# MCU_ATMEGA328P.net
KiCad netlist of a schematic drawn in Altium Designer
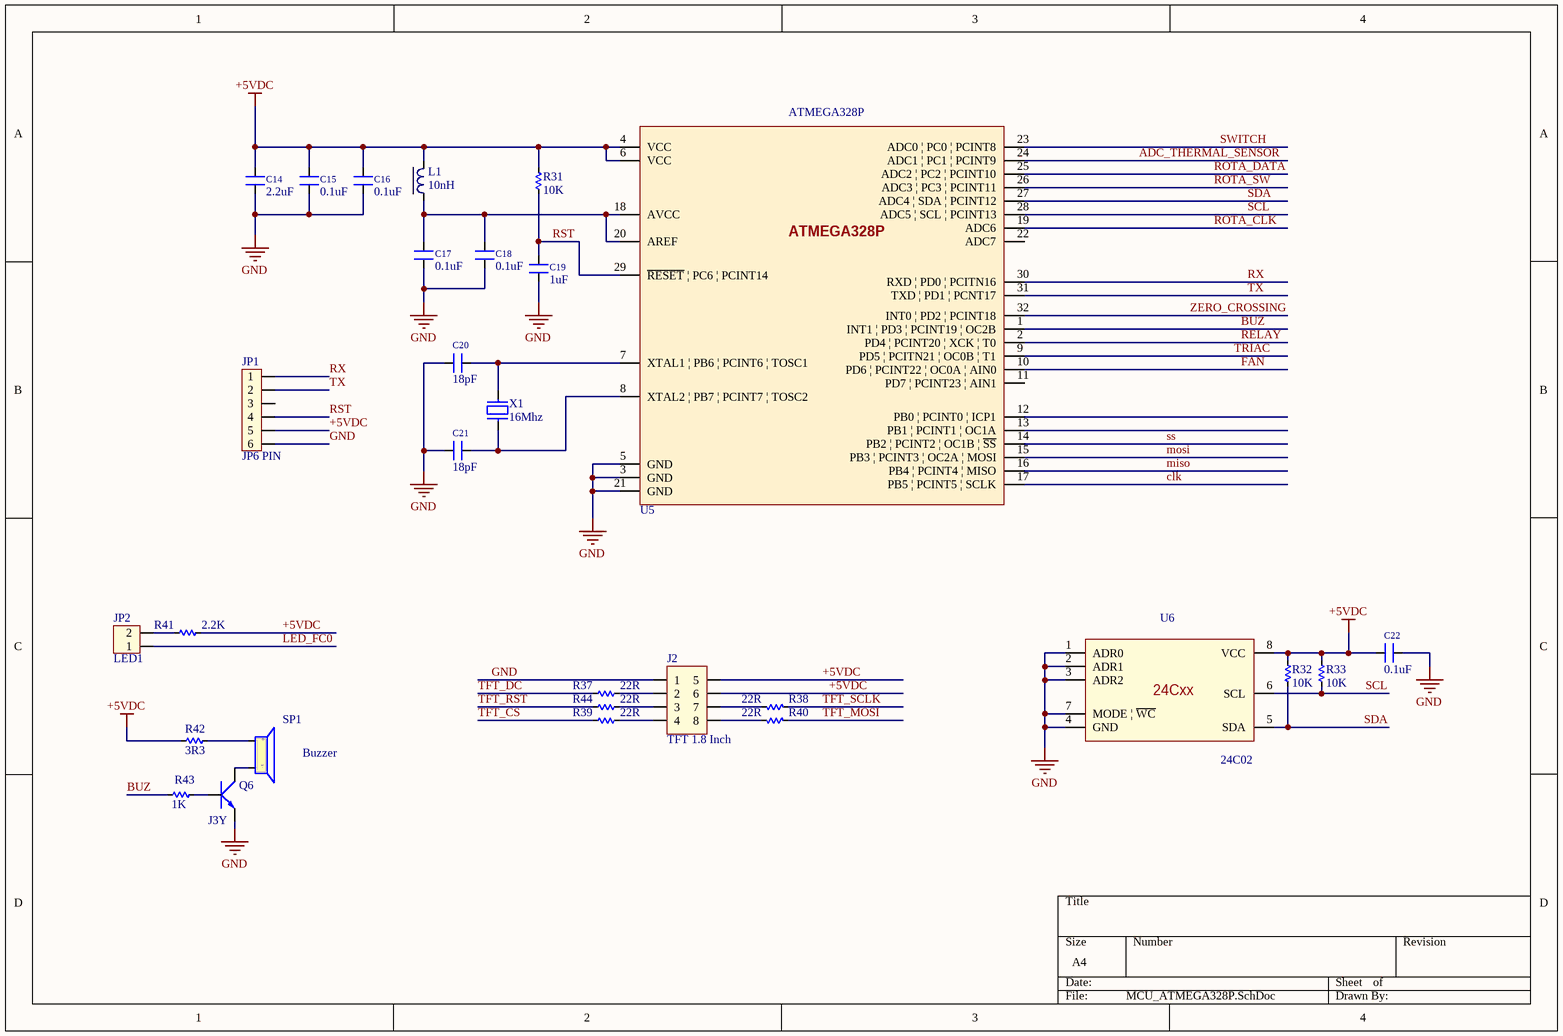
[diagram p0: MCU_ATMEGA328P.SchDoc]

(export (version "E")
  (design (tool "Eeschema 10.0.6"))
  (components
    (comp (ref "C14")
      (value "2.2uF")
      (footprint "CN-SMD-1206")
      (description "CAP SMD")
      (fields (field (name "DESIGNED BY") "VanDungEvn"))
      (libsource (lib "Sang_Library") (part "CAP SMD"))
    )
    (comp (ref "C15")
      (value "0.1uF")
      (footprint "CN-SMD-0805")
      (description "CAP SMD")
      (fields (field (name "DESIGNED BY") "VanDungEvn"))
      (libsource (lib "Sang_Library") (part "CAP SMD"))
    )
    (comp (ref "C16")
      (value "0.1uF")
      (footprint "CN-SMD-0805")
      (description "CAP SMD")
      (fields (field (name "DESIGNED BY") "VanDungEvn"))
      (libsource (lib "Sang_Library") (part "CAP SMD"))
    )
    (comp (ref "C17")
      (value "0.1uF")
      (footprint "CN-SMD-0805")
      (description "CAP SMD")
      (fields (field (name "DESIGNED BY") "VanDungEvn"))
      (libsource (lib "Sang_Library") (part "CAP SMD"))
    )
    (comp (ref "C18")
      (value "0.1uF")
      (footprint "CN-SMD-0805")
      (description "CAP SMD")
      (fields (field (name "DESIGNED BY") "VanDungEvn"))
      (libsource (lib "Sang_Library") (part "CAP SMD"))
    )
    (comp (ref "C19")
      (value "1uF")
      (footprint "CN-SMD-0805")
      (description "CAP SMD")
      (fields (field (name "DESIGNED BY") "VanDungEvn"))
      (libsource (lib "Sang_Library") (part "CAP SMD"))
    )
    (comp (ref "C20")
      (value "18pF")
      (footprint "CN-SMD-0805")
      (description "CAP SMD")
      (fields (field (name "DESIGNED BY") "VanDungEvn"))
      (libsource (lib "Sang_Library") (part "CAP SMD"))
    )
    (comp (ref "C21")
      (value "18pF")
      (footprint "CN-SMD-0805")
      (description "CAP SMD")
      (fields (field (name "DESIGNED BY") "VanDungEvn"))
      (libsource (lib "Sang_Library") (part "CAP SMD"))
    )
    (comp (ref "C22")
      (value "0.1uF")
      (footprint "CN-SMD-0805")
      (description "CAP SMD")
      (fields (field (name "DESIGNED BY") "VanDungEvn"))
      (libsource (lib "Sang_Library") (part "CAP SMD"))
    )
    (comp (ref "J2")
      (value "TFT 1.8 Inch")
      (footprint "JP4x2")
      (description "Connector 4x2")
      (libsource (lib "Sang_Library") (part "JP4x2"))
    )
    (comp (ref "JP1") (value "JP6 PIN") (footprint "JP6") (libsource (lib "Sang_Library") (part "JP6")))
    (comp (ref "JP2")
      (value "LED1")
      (footprint "CON2")
      (description "Connector 2")
      (libsource (lib "syhaunguyen") (part "Con2"))
    )
    (comp (ref "L1")
      (value "10nH")
      (footprint "IN-SMD-0805")
      (description "inductor-SMD")
      (libsource (lib "Sang_Library") (part "inductor-SMD"))
    )
    (comp (ref "Q6")
      (value "J3Y")
      (footprint "SOT23B")
      (description "NPN 600mW, ECB")
      (libsource (lib "Sang_Library") (part "2N222"))
    )
    (comp (ref "R31")
      (value "10K")
      (footprint "RES-SMD-0603")
      (description "Resistor")
      (fields
        (field (name "MANUFACTURER") "Generic Components")
        (field (name "PUBLISHER") "Altium Hobart Technology Centre")
      )
      (libsource (lib "Sang_Library") (part "Res-SMD"))
    )
    (comp (ref "R32")
      (value "10K")
      (footprint "RES-SMD-0603")
      (description "Resistor")
      (fields
        (field (name "MANUFACTURER") "Generic Components")
        (field (name "PUBLISHER") "Altium Hobart Technology Centre")
      )
      (libsource (lib "Sang_Library") (part "Res-SMD"))
    )
    (comp (ref "R33")
      (value "10K")
      (footprint "RES-SMD-0603")
      (description "Resistor")
      (fields
        (field (name "MANUFACTURER") "Generic Components")
        (field (name "PUBLISHER") "Altium Hobart Technology Centre")
      )
      (libsource (lib "Sang_Library") (part "Res-SMD"))
    )
    (comp (ref "R37")
      (value "22R")
      (footprint "RES-SMD-0603")
      (description "Resistor")
      (fields
        (field (name "MANUFACTURER") "Generic Components")
        (field (name "PUBLISHER") "Altium Hobart Technology Centre")
      )
      (libsource (lib "Sang_Library") (part "Res-SMD"))
    )
    (comp (ref "R38")
      (value "22R")
      (footprint "RES-SMD-0603")
      (description "Resistor")
      (fields
        (field (name "MANUFACTURER") "Generic Components")
        (field (name "PUBLISHER") "Altium Hobart Technology Centre")
      )
      (libsource (lib "Sang_Library") (part "Res-SMD"))
    )
    (comp (ref "R39")
      (value "22R")
      (footprint "RES-SMD-0603")
      (description "Resistor")
      (fields
        (field (name "MANUFACTURER") "Generic Components")
        (field (name "PUBLISHER") "Altium Hobart Technology Centre")
      )
      (libsource (lib "Sang_Library") (part "Res-SMD"))
    )
    (comp (ref "R40")
      (value "22R")
      (footprint "RES-SMD-0603")
      (description "Resistor")
      (fields
        (field (name "MANUFACTURER") "Generic Components")
        (field (name "PUBLISHER") "Altium Hobart Technology Centre")
      )
      (libsource (lib "Sang_Library") (part "Res-SMD"))
    )
    (comp (ref "R41")
      (value "2.2K")
      (footprint "RES-SMD-0603")
      (description "Resistor")
      (fields
        (field (name "MANUFACTURER") "Generic Components")
        (field (name "PUBLISHER") "Altium Hobart Technology Centre")
      )
      (libsource (lib "Sang_Library") (part "Res-SMD"))
    )
    (comp (ref "R42")
      (value "3R3")
      (footprint "RES-SMD-0805")
      (description "Resistor")
      (fields
        (field (name "MANUFACTURER") "Generic Components")
        (field (name "PUBLISHER") "Altium Hobart Technology Centre")
      )
      (libsource (lib "Sang_Library") (part "Res-SMD"))
    )
    (comp (ref "R43")
      (value "1K")
      (footprint "RES-SMD-0805")
      (description "Resistor")
      (fields
        (field (name "MANUFACTURER") "Generic Components")
        (field (name "PUBLISHER") "Altium Hobart Technology Centre")
      )
      (libsource (lib "Sang_Library") (part "Res-SMD"))
    )
    (comp (ref "R44")
      (value "22R")
      (footprint "RES-SMD-0603")
      (description "Resistor")
      (fields
        (field (name "MANUFACTURER") "Generic Components")
        (field (name "PUBLISHER") "Altium Hobart Technology Centre")
      )
      (libsource (lib "Sang_Library") (part "Res-SMD"))
    )
    (comp (ref "SP1") (value "Buzzer") (footprint "Buzzer") (libsource (lib "Huan") (part "Buzzer_5V")))
    (comp (ref "U5") (value "ATMEGA328P") (footprint "TQFP-32") (libsource (lib "Huan") (part "ATMEGA328p")))
    (comp (ref "U6")
      (value "24C02")
      (footprint "SOP-8")
      (description "SERIAL EEPROM")
      (libsource (lib "Huan") (part "24Cxx"))
    )
    (comp (ref "X1")
      (value "16Mhz")
      (footprint "XT-49S/DIP")
      (description "crystal")
      (libsource (lib "Sang_Library") (part "XTAL"))
    )
  )
  (nets
    (net (code "1") (name "+5VDC") (class "Default")
      (node (ref "C14") (pin "2") (pinfunction "2_2") (pintype "passive"))
      (node (ref "C15") (pin "2") (pinfunction "2_2") (pintype "passive"))
      (node (ref "C16") (pin "2") (pinfunction "2_2") (pintype "passive"))
      (node (ref "C22") (pin "2") (pinfunction "2_2") (pintype "passive"))
      (node (ref "J2") (pin "5") (pinfunction "5_5") (pintype "passive"))
      (node (ref "J2") (pin "6") (pinfunction "6_6") (pintype "passive"))
      (node (ref "JP1") (pin "5") (pinfunction "5_5") (pintype "passive"))
      (node (ref "L1") (pin "2") (pinfunction "2_2") (pintype "passive"))
      (node (ref "R31") (pin "1") (pinfunction "1_1") (pintype "passive"))
      (node (ref "R32") (pin "1") (pinfunction "1_1") (pintype "passive"))
      (node (ref "R33") (pin "1") (pinfunction "1_1") (pintype "passive"))
      (node (ref "R41") (pin "2") (pinfunction "2_2") (pintype "passive"))
      (node (ref "R42") (pin "1") (pinfunction "1_1") (pintype "passive"))
      (node (ref "U5") (pin "4") (pinfunction "VCC_4") (pintype "passive"))
      (node (ref "U5") (pin "6") (pinfunction "VCC_6") (pintype "passive"))
      (node (ref "U6") (pin "8") (pinfunction "VCC_8") (pintype "passive"))
    )
    (net (code "3") (name "/ADC_THERMAL_SENSOR") (class "Default")
      (node (ref "U5") (pin "24") (pinfunction "ADC1_¦_PC1_¦_PCINT9_24") (pintype "passive"))
    )
    (net (code "4") (name "/BUZ") (class "Default")
      (node (ref "R43") (pin "2") (pinfunction "2_2") (pintype "passive"))
      (node (ref "U5") (pin "1") (pinfunction "INT1_¦_PD3_¦_PCINT19_¦_OC2B_1") (pintype "power_in"))
    )
    (net (code "5") (name "/FAN") (class "Default")
      (node (ref "U5") (pin "10") (pinfunction "PD6_¦_PCINT22_¦_OC0A_¦_AIN0_10") (pintype "power_in"))
    )
    (net (code "6") (name "/LED_FC0") (class "Default")
      (node (ref "JP2") (pin "1") (pinfunction "1_1") (pintype "passive"))
    )
    (net (code "7") (name "/RELAY") (class "Default")
      (node (ref "U5") (pin "2") (pinfunction "PD4_¦_PCINT20_¦_XCK_¦_T0_2") (pintype "passive"))
    )
    (net (code "8") (name "/ROTA_CLK") (class "Default")
      (node (ref "U5") (pin "19") (pinfunction "ADC6_19") (pintype "passive"))
    )
    (net (code "9") (name "/ROTA_DATA") (class "Default")
      (node (ref "U5") (pin "25") (pinfunction "ADC2_¦_PC2_¦_PCINT10_25") (pintype "passive"))
    )
    (net (code "10") (name "/ROTA_SW") (class "Default")
      (node (ref "U5") (pin "26") (pinfunction "ADC3_¦_PC3_¦_PCINT11_26") (pintype "passive"))
    )
    (net (code "11") (name "/RST") (class "Default")
      (node (ref "C19") (pin "2") (pinfunction "2_2") (pintype "passive"))
      (node (ref "JP1") (pin "4") (pinfunction "4_4") (pintype "passive"))
      (node (ref "R31") (pin "2") (pinfunction "2_2") (pintype "passive"))
      (node (ref "U5") (pin "29") (pinfunction "~{RESET}_¦_PC6_¦_PCINT14_29") (pintype "passive"))
    )
    (net (code "12") (name "/RX") (class "Default")
      (node (ref "JP1") (pin "1") (pinfunction "1_1") (pintype "passive"))
      (node (ref "U5") (pin "30") (pinfunction "RXD_¦_PD0_¦_PCITN16_30") (pintype "passive"))
    )
    (net (code "13") (name "/SCL") (class "Default")
      (node (ref "R33") (pin "2") (pinfunction "2_2") (pintype "passive"))
      (node (ref "U5") (pin "28") (pinfunction "ADC5_¦_SCL_¦_PCINT13_28") (pintype "passive"))
      (node (ref "U6") (pin "6") (pinfunction "SCL_6") (pintype "passive"))
    )
    (net (code "14") (name "/SDA") (class "Default")
      (node (ref "R32") (pin "2") (pinfunction "2_2") (pintype "passive"))
      (node (ref "U5") (pin "27") (pinfunction "ADC4_¦_SDA_¦_PCINT12_27") (pintype "passive"))
      (node (ref "U6") (pin "5") (pinfunction "SDA_5") (pintype "passive"))
    )
    (net (code "15") (name "/SWITCH") (class "Default")
      (node (ref "U5") (pin "23") (pinfunction "ADC0_¦_PC0_¦_PCINT8_23") (pintype "passive"))
    )
    (net (code "16") (name "/TFT_CS") (class "Default")
      (node (ref "R39") (pin "1") (pinfunction "1_1") (pintype "passive"))
    )
    (net (code "17") (name "/TFT_DC") (class "Default")
      (node (ref "R37") (pin "1") (pinfunction "1_1") (pintype "passive"))
    )
    (net (code "18") (name "/TFT_MOSI") (class "Default")
      (node (ref "R40") (pin "1") (pinfunction "1_1") (pintype "passive"))
    )
    (net (code "19") (name "/TFT_RST") (class "Default")
      (node (ref "R44") (pin "1") (pinfunction "1_1") (pintype "passive"))
    )
    (net (code "20") (name "/TFT_SCLK") (class "Default")
      (node (ref "R38") (pin "1") (pinfunction "1_1") (pintype "passive"))
    )
    (net (code "21") (name "/TRIAC") (class "Default")
      (node (ref "U5") (pin "9") (pinfunction "PD5_¦_PCITN21_¦_OC0B_¦_T1_9") (pintype "power_in"))
    )
    (net (code "22") (name "/TX") (class "Default")
      (node (ref "JP1") (pin "2") (pinfunction "2_2") (pintype "passive"))
      (node (ref "U5") (pin "31") (pinfunction "TXD_¦_PD1_¦_PCNT17_31") (pintype "passive"))
    )
    (net (code "23") (name "/ZERO_CROSSING") (class "Default")
      (node (ref "U5") (pin "32") (pinfunction "INT0_¦_PD2_¦_PCINT18_32") (pintype "passive"))
    )
    (net (code "24") (name "/clk") (class "Default")
      (node (ref "U5") (pin "17") (pinfunction "PB5_¦_PCINT5_¦_SCLK_17") (pintype "passive"))
    )
    (net (code "25") (name "/miso") (class "Default")
      (node (ref "U5") (pin "16") (pinfunction "PB4_¦_PCINT4_¦_MISO_16") (pintype "passive"))
    )
    (net (code "26") (name "/mosi") (class "Default")
      (node (ref "U5") (pin "15") (pinfunction "PB3_¦_PCINT3_¦_OC2A_¦_MOSI_15") (pintype "power_in"))
    )
    (net (code "27") (name "/ss") (class "Default")
      (node (ref "U5") (pin "14") (pinfunction "PB2_¦_PCINT2_¦_OC1B_¦_~{SS}_14") (pintype "power_in"))
    )
    (net (code "28") (name "GND") (class "Default")
      (node (ref "C14") (pin "1") (pinfunction "1_1") (pintype "passive"))
      (node (ref "C15") (pin "1") (pinfunction "1_1") (pintype "passive"))
      (node (ref "C16") (pin "1") (pinfunction "1_1") (pintype "passive"))
      (node (ref "C17") (pin "1") (pinfunction "1_1") (pintype "passive"))
      (node (ref "C18") (pin "1") (pinfunction "1_1") (pintype "passive"))
      (node (ref "C19") (pin "1") (pinfunction "1_1") (pintype "passive"))
      (node (ref "C20") (pin "2") (pinfunction "2_2") (pintype "passive"))
      (node (ref "C21") (pin "2") (pinfunction "2_2") (pintype "passive"))
      (node (ref "C22") (pin "1") (pinfunction "1_1") (pintype "passive"))
      (node (ref "J2") (pin "1") (pinfunction "1_1") (pintype "passive"))
      (node (ref "JP1") (pin "6") (pinfunction "6_6") (pintype "passive"))
      (node (ref "Q6") (pin "1") (pinfunction "E_1") (pintype "passive"))
      (node (ref "U5") (pin "21") (pinfunction "GND_21") (pintype "passive"))
      (node (ref "U5") (pin "3") (pinfunction "GND_3") (pintype "passive"))
      (node (ref "U5") (pin "5") (pinfunction "GND_5") (pintype "passive"))
      (node (ref "U6") (pin "1") (pinfunction "ADR0_1") (pintype "passive"))
      (node (ref "U6") (pin "2") (pinfunction "ADR1_2") (pintype "passive"))
      (node (ref "U6") (pin "3") (pinfunction "ADR2_3") (pintype "passive"))
      (node (ref "U6") (pin "4") (pinfunction "GND_4") (pintype "passive"))
      (node (ref "U6") (pin "7") (pinfunction "MODE_¦_~{WC}_7") (pintype "passive"))
    )
    (net (code "29") (name "Net-(J2-Pad2)") (class "Default")
      (node (ref "J2") (pin "2") (pinfunction "2_2") (pintype "passive"))
      (node (ref "R37") (pin "2") (pinfunction "2_2") (pintype "passive"))
    )
    (net (code "30") (name "Net-(J2-Pad3)") (class "Default")
      (node (ref "J2") (pin "3") (pinfunction "3_3") (pintype "passive"))
      (node (ref "R44") (pin "2") (pinfunction "2_2") (pintype "passive"))
    )
    (net (code "31") (name "Net-(J2-Pad4)") (class "Default")
      (node (ref "J2") (pin "4") (pinfunction "4_4") (pintype "passive"))
      (node (ref "R39") (pin "2") (pinfunction "2_2") (pintype "passive"))
    )
    (net (code "32") (name "Net-(J2-Pad7)") (class "Default")
      (node (ref "J2") (pin "7") (pinfunction "7_7") (pintype "passive"))
      (node (ref "R38") (pin "2") (pinfunction "2_2") (pintype "passive"))
    )
    (net (code "33") (name "Net-(J2-Pad8)") (class "Default")
      (node (ref "J2") (pin "8") (pinfunction "8_8") (pintype "passive"))
      (node (ref "R40") (pin "2") (pinfunction "2_2") (pintype "passive"))
    )
    (net (code "34") (name "Net-(JP2-Pad2)") (class "Default")
      (node (ref "JP2") (pin "2") (pinfunction "2_2") (pintype "passive"))
      (node (ref "R41") (pin "1") (pinfunction "1_1") (pintype "passive"))
    )
    (net (code "35") (name "Net-(Q6-B)") (class "Default")
      (node (ref "Q6") (pin "2") (pinfunction "B_2") (pintype "passive"))
      (node (ref "R43") (pin "1") (pinfunction "1_1") (pintype "passive"))
    )
    (net (code "36") (name "Net-(Q6-C)") (class "Default")
      (node (ref "Q6") (pin "3") (pinfunction "C_3") (pintype "passive"))
      (node (ref "SP1") (pin "2") (pinfunction "2_2") (pintype "passive"))
    )
    (net (code "37") (name "Net-(R42-Pad2)") (class "Default")
      (node (ref "R42") (pin "2") (pinfunction "2_2") (pintype "passive"))
      (node (ref "SP1") (pin "1") (pinfunction "1_1") (pintype "passive"))
    )
    (net (code "38") (name "Net-(U5-AREF)") (class "Default")
      (node (ref "C17") (pin "2") (pinfunction "2_2") (pintype "passive"))
      (node (ref "C18") (pin "2") (pinfunction "2_2") (pintype "passive"))
      (node (ref "L1") (pin "1") (pinfunction "1_1") (pintype "passive"))
      (node (ref "U5") (pin "18") (pinfunction "AVCC_18") (pintype "passive"))
      (node (ref "U5") (pin "20") (pinfunction "AREF_20") (pintype "passive"))
    )
    (net (code "39") (name "Net-(U5-XTAL1_¦_PB6_¦_PCINT6_¦_TOSC1)") (class "Default")
      (node (ref "C20") (pin "1") (pinfunction "1_1") (pintype "passive"))
      (node (ref "U5") (pin "7") (pinfunction "XTAL1_¦_PB6_¦_PCINT6_¦_TOSC1_7") (pintype "passive"))
      (node (ref "X1") (pin "1") (pinfunction "1_1") (pintype "passive"))
    )
    (net (code "40") (name "Net-(U5-XTAL2_¦_PB7_¦_PCINT7_¦_TOSC2)") (class "Default")
      (node (ref "C21") (pin "1") (pinfunction "1_1") (pintype "passive"))
      (node (ref "U5") (pin "8") (pinfunction "XTAL2_¦_PB7_¦_PCINT7_¦_TOSC2_8") (pintype "passive"))
      (node (ref "X1") (pin "2") (pinfunction "2_2") (pintype "passive"))
    )
    (net (code "41") (name "unconnected-(JP1-Pad3)") (class "Default")
      (node (ref "JP1") (pin "3") (pinfunction "3_3") (pintype "passive"))
    )
    (net (code "42") (name "unconnected-(U5-ADC7-Pad22)") (class "Default")
      (node (ref "U5") (pin "22") (pinfunction "ADC7_22") (pintype "passive"))
    )
    (net (code "43") (name "unconnected-(U5-PB0_¦_PCINT0_¦_ICP1-Pad12)") (class "Default")
      (node (ref "U5") (pin "12") (pinfunction "PB0_¦_PCINT0_¦_ICP1_12") (pintype "passive"))
    )
    (net (code "44") (name "unconnected-(U5-PB1_¦_PCINT1_¦_OC1A-Pad13)") (class "Default")
      (node (ref "U5") (pin "13") (pinfunction "PB1_¦_PCINT1_¦_OC1A_13") (pintype "power_in"))
    )
    (net (code "45") (name "unconnected-(U5-PD7_¦_PCINT23_¦_AIN1-Pad11)") (class "Default")
      (node (ref "U5") (pin "11") (pinfunction "PD7_¦_PCINT23_¦_AIN1_11") (pintype "passive"))
    )
  )
)
